# BatteryConn_Protection.net
KiCad netlist of a schematic drawn in Altium Designer
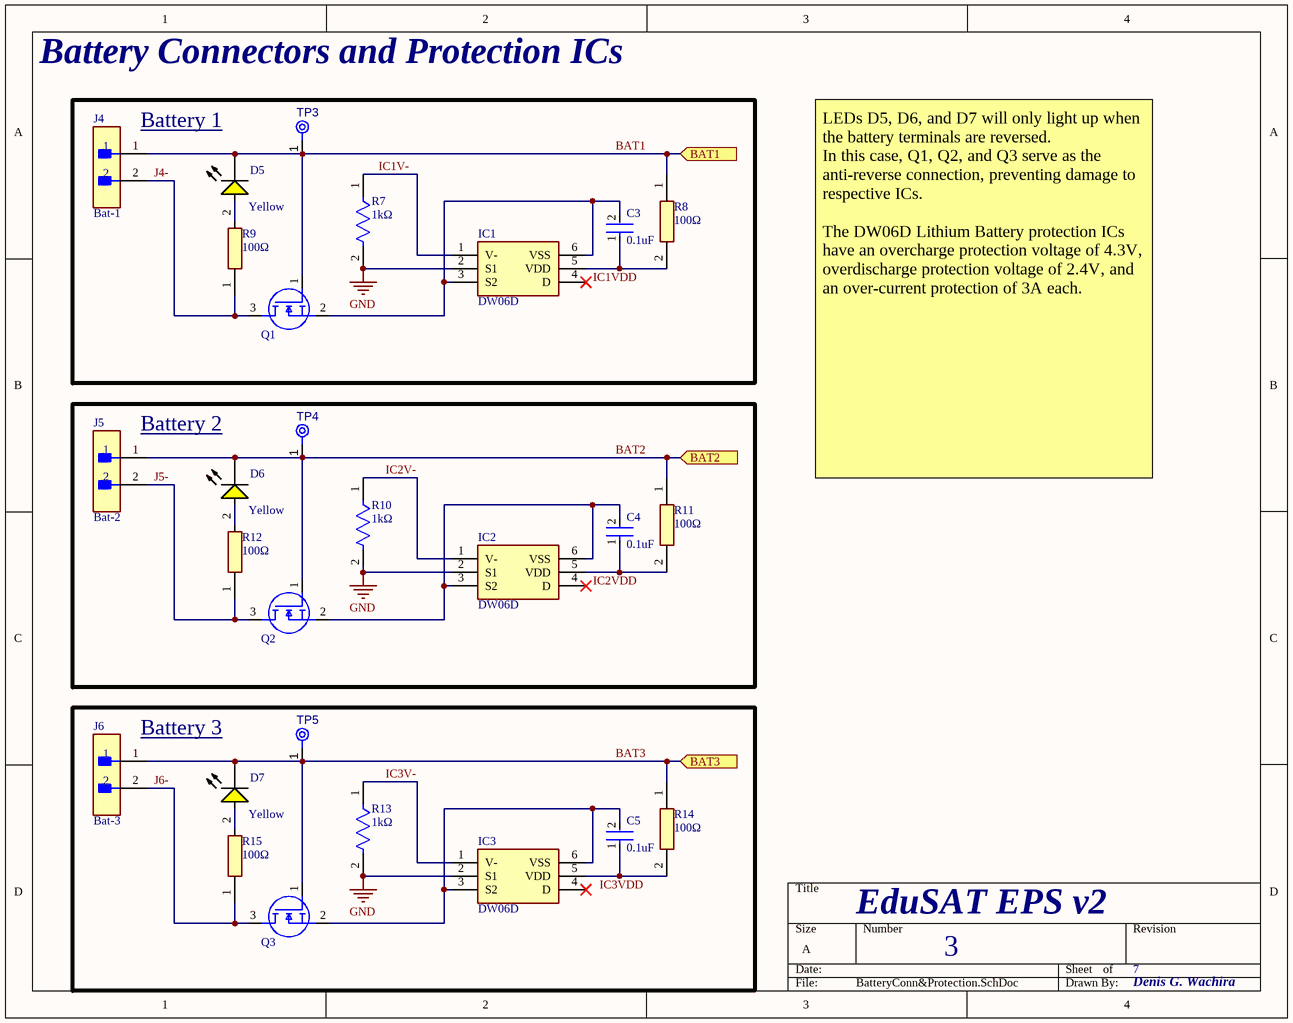
[diagram p0: BatteryConn&Protection.SchDoc]

(export (version "E")
  (design (tool "Eeschema 10.0.6"))
  (components
    (comp (ref "C3")
      (value "0.1uF")
      (footprint "FP-CL21-IPC_A")
      (description "50V 0.1uF X7R ±10% 0805 Multilayer Ceramic Capacitors MLCC - SMD/SMT ROHS TCC0805X7R104K500DT")
      (fields (field (name "TOLERANCE") "10%"))
      (libsource (lib "Altium Content Vault") (part "b4654b650e69147ec39a6b967a45e02"))
    )
    (comp (ref "C4")
      (value "0.1uF")
      (footprint "FP-CL21-IPC_A")
      (description "50V 0.1uF X7R ±10% 0805 Multilayer Ceramic Capacitors MLCC - SMD/SMT ROHS TCC0805X7R104K500DT")
      (fields (field (name "TOLERANCE") "10%"))
      (libsource (lib "Altium Content Vault") (part "b4654b650e69147ec39a6b967a45e02"))
    )
    (comp (ref "C5")
      (value "0.1uF")
      (footprint "FP-CL21-IPC_A")
      (description "50V 0.1uF X7R ±10% 0805 Multilayer Ceramic Capacitors MLCC - SMD/SMT ROHS TCC0805X7R104K500DT")
      (fields (field (name "TOLERANCE") "10%"))
      (libsource (lib "Altium Content Vault") (part "b4654b650e69147ec39a6b967a45e02"))
    )
    (comp (ref "D5")
      (value "Yellow")
      (footprint "LTST-C170KSKT_V")
      (description "LED Yellow, 75 mW, 80 mA, -55 to 85 degC, 2-Pin SMD, RoHS, Tape and Reel KT-0805Y")
      (fields (field (name "MANUFACTURER") "Lite-On"))
      (libsource (lib "Altium Content Vault") (part "LED-YELLOW-AK-2"))
    )
    (comp (ref "D6")
      (value "Yellow")
      (footprint "LTST-C170KSKT_V")
      (description "LED Yellow, 75 mW, 80 mA, -55 to 85 degC, 2-Pin SMD, RoHS, Tape and Reel KT-0805Y")
      (fields (field (name "MANUFACTURER") "Lite-On"))
      (libsource (lib "Altium Content Vault") (part "LED-YELLOW-AK-2"))
    )
    (comp (ref "D7")
      (value "Yellow")
      (footprint "LTST-C170KSKT_V")
      (description "LED Yellow, 75 mW, 80 mA, -55 to 85 degC, 2-Pin SMD, RoHS, Tape and Reel KT-0805Y")
      (fields (field (name "MANUFACTURER") "Lite-On"))
      (libsource (lib "Altium Content Vault") (part "LED-YELLOW-AK-2"))
    )
    (comp (ref "IC1")
      (value "DW06D")
      (footprint "SamacSys:SOT95P280X135-6N")
      (description "Integrated Circuit")
      (libsource (lib "*") (part "DW06D"))
    )
    (comp (ref "IC2")
      (value "DW06D")
      (footprint "SamacSys:SOT95P280X135-6N")
      (description "Integrated Circuit")
      (libsource (lib "*") (part "DW06D"))
    )
    (comp (ref "IC3")
      (value "DW06D")
      (footprint "SamacSys:SOT95P280X135-6N")
      (description "Integrated Circuit")
      (libsource (lib "*") (part "DW06D"))
    )
    (comp (ref "J4")
      (value "Bat-1")
      (footprint "FP-S2B-XH-A-1_LF_SN-MFG")
      (description "CONN HEADER R/A 2POS 2.5MM HCZZ0139-2")
      (libsource (lib "Altium Content Vault") (part "3bc925449376181038e59eaffc5286c"))
    )
    (comp (ref "J5")
      (value "Bat-2")
      (footprint "FP-S2B-XH-A-1_LF_SN-MFG")
      (description "CONN HEADER R/A 2POS 2.5MM HCZZ0139-2")
      (libsource (lib "Altium Content Vault") (part "3bc925449376181038e59eaffc5286c"))
    )
    (comp (ref "J6")
      (value "Bat-3")
      (footprint "FP-S2B-XH-A-1_LF_SN-MFG")
      (description "CONN HEADER R/A 2POS 2.5MM HCZZ0139-2")
      (libsource (lib "Altium Content Vault") (part "3bc925449376181038e59eaffc5286c"))
    )
    (comp (ref "Q1")
      (value "~")
      (footprint "SamacSys:SOT95P237X112-3N")
      (description "MOSFET (N-Channel)IRLML6344TRPBF")
      (fields
        (field (name "MANUFACTURER_PART_NUMBER") "IRLML6344TRPBF")
        (field (name "MOUSER PART NUMBER") "942-IRLML6344TRPBF")
      )
      (libsource (lib "*") (part "IRLML6344TRPBF"))
    )
    (comp (ref "Q2")
      (value "~")
      (footprint "SamacSys:SOT95P237X112-3N")
      (description "MOSFET (N-Channel)IRLML6344TRPBF")
      (fields
        (field (name "MANUFACTURER_PART_NUMBER") "IRLML6344TRPBF")
        (field (name "MOUSER PART NUMBER") "942-IRLML6344TRPBF")
      )
      (libsource (lib "*") (part "IRLML6344TRPBF"))
    )
    (comp (ref "Q3")
      (value "~")
      (footprint "SamacSys:SOT95P237X112-3N")
      (description "MOSFET (N-Channel)IRLML6344TRPBF")
      (fields
        (field (name "MANUFACTURER_PART_NUMBER") "IRLML6344TRPBF")
        (field (name "MOUSER PART NUMBER") "942-IRLML6344TRPBF")
      )
      (libsource (lib "*") (part "IRLML6344TRPBF"))
    )
    (comp (ref "R7")
      (value "1kΩ")
      (footprint "FP-MCR10-IPC_A")
      (description "Thick Film Chip Resistor, 0805, 1kΩ, 1%, 100ppm/°C, 0.125W, 150V 0805W8F1001T5E")
      (fields (field (name "TOLERANCE") "1%"))
      (libsource (lib "Altium Content Vault") (part "1029c3af85768c4190bb7ad29bc67b5"))
    )
    (comp (ref "R8")
      (value "100Ω")
      (footprint "SamacSys:RESC2012X65N")
      (fields (field (name "MANUFACTURER_PART_NUMBER") "AECR0805F27R0K9"))
      (libsource (lib "") (part "AECR0805F27R0K9_1"))
    )
    (comp (ref "R9")
      (value "100Ω")
      (footprint "SamacSys:RESC2012X65N")
      (fields (field (name "MANUFACTURER_PART_NUMBER") "AECR0805F27R0K9"))
      (libsource (lib "*") (part "AECR0805F27R0K9"))
    )
    (comp (ref "R10")
      (value "1kΩ")
      (footprint "FP-MCR10-IPC_A")
      (description "Thick Film Chip Resistor, 0805, 1kΩ, 1%, 100ppm/°C, 0.125W, 150V 0805W8F1001T5E")
      (fields (field (name "TOLERANCE") "1%"))
      (libsource (lib "Altium Content Vault") (part "1029c3af85768c4190bb7ad29bc67b5"))
    )
    (comp (ref "R11")
      (value "100Ω")
      (footprint "SamacSys:RESC2012X65N")
      (fields (field (name "MANUFACTURER_PART_NUMBER") "AECR0805F27R0K9"))
      (libsource (lib "") (part "AECR0805F27R0K9_1"))
    )
    (comp (ref "R12")
      (value "100Ω")
      (footprint "SamacSys:RESC2012X65N")
      (fields (field (name "MANUFACTURER_PART_NUMBER") "AECR0805F27R0K9"))
      (libsource (lib "*") (part "AECR0805F27R0K9"))
    )
    (comp (ref "R13")
      (value "1kΩ")
      (footprint "FP-MCR10-IPC_A")
      (description "Thick Film Chip Resistor, 0805, 1kΩ, 1%, 100ppm/°C, 0.125W, 150V 0805W8F1001T5E")
      (fields (field (name "TOLERANCE") "1%"))
      (libsource (lib "Altium Content Vault") (part "1029c3af85768c4190bb7ad29bc67b5"))
    )
    (comp (ref "R14")
      (value "100Ω")
      (footprint "SamacSys:RESC2012X65N")
      (fields (field (name "MANUFACTURER_PART_NUMBER") "AECR0805F27R0K9"))
      (libsource (lib "") (part "AECR0805F27R0K9_1"))
    )
    (comp (ref "R15")
      (value "100Ω")
      (footprint "SamacSys:RESC2012X65N")
      (fields (field (name "MANUFACTURER_PART_NUMBER") "AECR0805F27R0K9"))
      (libsource (lib "*") (part "AECR0805F27R0K9"))
    )
    (comp (ref "TP3")
      (value "TPAD6R")
      (footprint "TP06R")
      (description "0.6mm round")
      (libsource (lib "University of Nairobi") (part "CMP-001-0001-4"))
    )
    (comp (ref "TP4")
      (value "TPAD6R")
      (footprint "TP06R")
      (description "0.6mm round")
      (libsource (lib "University of Nairobi") (part "CMP-001-0001-4"))
    )
    (comp (ref "TP5")
      (value "TPAD6R")
      (footprint "TP06R")
      (description "0.6mm round")
      (libsource (lib "University of Nairobi") (part "CMP-001-0001-4"))
    )
  )
  (nets
    (net (code "1") (name "/BAT1") (class "Default")
      (node (ref "D5") (pin "2") (pinfunction "K_2") (pintype "passive"))
      (node (ref "J4") (pin "1") (pinfunction "1_1") (pintype "passive"))
      (node (ref "Q1") (pin "1") (pinfunction "G_1") (pintype "passive"))
      (node (ref "R8") (pin "1") (pinfunction "1_1") (pintype "passive"))
      (node (ref "TP3") (pin "1") (pinfunction "TP_1") (pintype "passive"))
    )
    (net (code "2") (name "/BAT2") (class "Default")
      (node (ref "D6") (pin "2") (pinfunction "K_2") (pintype "passive"))
      (node (ref "J5") (pin "1") (pinfunction "1_1") (pintype "passive"))
      (node (ref "Q2") (pin "1") (pinfunction "G_1") (pintype "passive"))
      (node (ref "R11") (pin "1") (pinfunction "1_1") (pintype "passive"))
      (node (ref "TP4") (pin "1") (pinfunction "TP_1") (pintype "passive"))
    )
    (net (code "3") (name "/BAT3") (class "Default")
      (node (ref "D7") (pin "2") (pinfunction "K_2") (pintype "passive"))
      (node (ref "J6") (pin "1") (pinfunction "1_1") (pintype "passive"))
      (node (ref "Q3") (pin "1") (pinfunction "G_1") (pintype "passive"))
      (node (ref "R14") (pin "1") (pinfunction "1_1") (pintype "passive"))
      (node (ref "TP5") (pin "1") (pinfunction "TP_1") (pintype "passive"))
    )
    (net (code "4") (name "/IC1V-") (class "Default")
      (node (ref "IC1") (pin "1") (pinfunction "V-_1") (pintype "passive"))
      (node (ref "R7") (pin "1") (pinfunction "1_1") (pintype "passive"))
    )
    (net (code "5") (name "/IC1VDD") (class "Default")
      (node (ref "C3") (pin "1") (pinfunction "1_1") (pintype "passive"))
      (node (ref "IC1") (pin "5") (pinfunction "VDD_5") (pintype "passive"))
      (node (ref "R8") (pin "2") (pinfunction "2_2") (pintype "passive"))
    )
    (net (code "6") (name "/IC2V-") (class "Default")
      (node (ref "IC2") (pin "1") (pinfunction "V-_1") (pintype "passive"))
      (node (ref "R10") (pin "1") (pinfunction "1_1") (pintype "passive"))
    )
    (net (code "7") (name "/IC2VDD") (class "Default")
      (node (ref "C4") (pin "1") (pinfunction "1_1") (pintype "passive"))
      (node (ref "IC2") (pin "5") (pinfunction "VDD_5") (pintype "passive"))
      (node (ref "R11") (pin "2") (pinfunction "2_2") (pintype "passive"))
    )
    (net (code "8") (name "/IC3V-") (class "Default")
      (node (ref "IC3") (pin "1") (pinfunction "V-_1") (pintype "passive"))
      (node (ref "R13") (pin "1") (pinfunction "1_1") (pintype "passive"))
    )
    (net (code "9") (name "/IC3VDD") (class "Default")
      (node (ref "C5") (pin "1") (pinfunction "1_1") (pintype "passive"))
      (node (ref "IC3") (pin "5") (pinfunction "VDD_5") (pintype "passive"))
      (node (ref "R14") (pin "2") (pinfunction "2_2") (pintype "passive"))
    )
    (net (code "10") (name "/J4-") (class "Default")
      (node (ref "J4") (pin "2") (pinfunction "2_2") (pintype "passive"))
      (node (ref "Q1") (pin "3") (pinfunction "D_3") (pintype "passive"))
      (node (ref "R9") (pin "1") (pinfunction "1_1") (pintype "passive"))
    )
    (net (code "11") (name "/J5-") (class "Default")
      (node (ref "J5") (pin "2") (pinfunction "2_2") (pintype "passive"))
      (node (ref "Q2") (pin "3") (pinfunction "D_3") (pintype "passive"))
      (node (ref "R12") (pin "1") (pinfunction "1_1") (pintype "passive"))
    )
    (net (code "12") (name "/J6-") (class "Default")
      (node (ref "J6") (pin "2") (pinfunction "2_2") (pintype "passive"))
      (node (ref "Q3") (pin "3") (pinfunction "D_3") (pintype "passive"))
      (node (ref "R15") (pin "1") (pinfunction "1_1") (pintype "passive"))
    )
    (net (code "13") (name "GND") (class "Default")
      (node (ref "IC1") (pin "2") (pinfunction "S1_2") (pintype "passive"))
      (node (ref "IC2") (pin "2") (pinfunction "S1_2") (pintype "passive"))
      (node (ref "IC3") (pin "2") (pinfunction "S1_2") (pintype "passive"))
      (node (ref "R10") (pin "2") (pinfunction "2_2") (pintype "passive"))
      (node (ref "R13") (pin "2") (pinfunction "2_2") (pintype "passive"))
      (node (ref "R7") (pin "2") (pinfunction "2_2") (pintype "passive"))
    )
    (net (code "14") (name "Net-(D5-A)") (class "Default")
      (node (ref "D5") (pin "1") (pinfunction "A_1") (pintype "passive"))
      (node (ref "R9") (pin "2") (pinfunction "2_2") (pintype "passive"))
    )
    (net (code "15") (name "Net-(D6-A)") (class "Default")
      (node (ref "D6") (pin "1") (pinfunction "A_1") (pintype "passive"))
      (node (ref "R12") (pin "2") (pinfunction "2_2") (pintype "passive"))
    )
    (net (code "16") (name "Net-(D7-A)") (class "Default")
      (node (ref "D7") (pin "1") (pinfunction "A_1") (pintype "passive"))
      (node (ref "R15") (pin "2") (pinfunction "2_2") (pintype "passive"))
    )
    (net (code "17") (name "Net-(IC1-S2)") (class "Default")
      (node (ref "C3") (pin "2") (pinfunction "2_2") (pintype "passive"))
      (node (ref "IC1") (pin "3") (pinfunction "S2_3") (pintype "passive"))
      (node (ref "IC1") (pin "6") (pinfunction "VSS_6") (pintype "passive"))
      (node (ref "Q1") (pin "2") (pinfunction "S_2") (pintype "passive"))
    )
    (net (code "18") (name "Net-(IC2-S2)") (class "Default")
      (node (ref "C4") (pin "2") (pinfunction "2_2") (pintype "passive"))
      (node (ref "IC2") (pin "3") (pinfunction "S2_3") (pintype "passive"))
      (node (ref "IC2") (pin "6") (pinfunction "VSS_6") (pintype "passive"))
      (node (ref "Q2") (pin "2") (pinfunction "S_2") (pintype "passive"))
    )
    (net (code "19") (name "Net-(IC3-S2)") (class "Default")
      (node (ref "C5") (pin "2") (pinfunction "2_2") (pintype "passive"))
      (node (ref "IC3") (pin "3") (pinfunction "S2_3") (pintype "passive"))
      (node (ref "IC3") (pin "6") (pinfunction "VSS_6") (pintype "passive"))
      (node (ref "Q3") (pin "2") (pinfunction "S_2") (pintype "passive"))
    )
    (net (code "20") (name "unconnected-(IC1-D-Pad4)") (class "Default")
      (node (ref "IC1") (pin "4") (pinfunction "D_4") (pintype "passive+no_connect"))
    )
    (net (code "21") (name "unconnected-(IC2-D-Pad4)") (class "Default")
      (node (ref "IC2") (pin "4") (pinfunction "D_4") (pintype "passive+no_connect"))
    )
    (net (code "22") (name "unconnected-(IC3-D-Pad4)") (class "Default")
      (node (ref "IC3") (pin "4") (pinfunction "D_4") (pintype "passive+no_connect"))
    )
  )
)
